# FPGA_MISC.net
KiCad netlist of a schematic drawn in Altium Designer
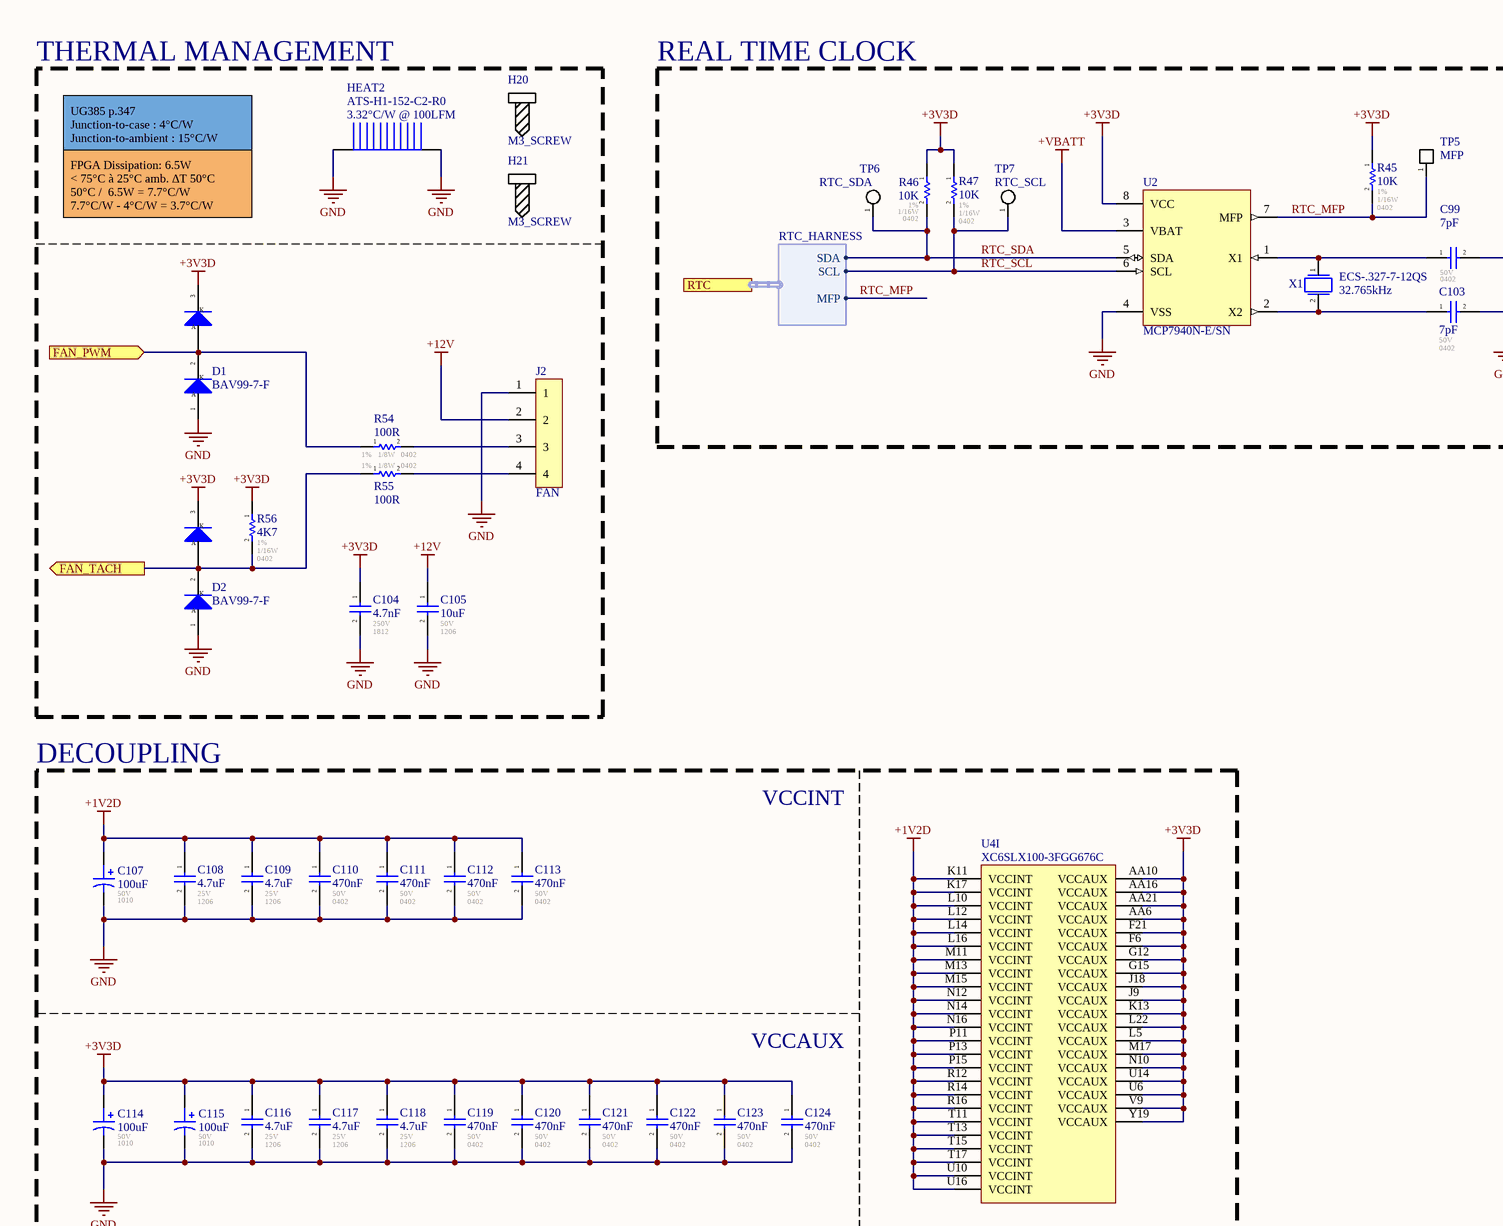
[diagram p0: FPGA_MISC.SchDoc, top left]
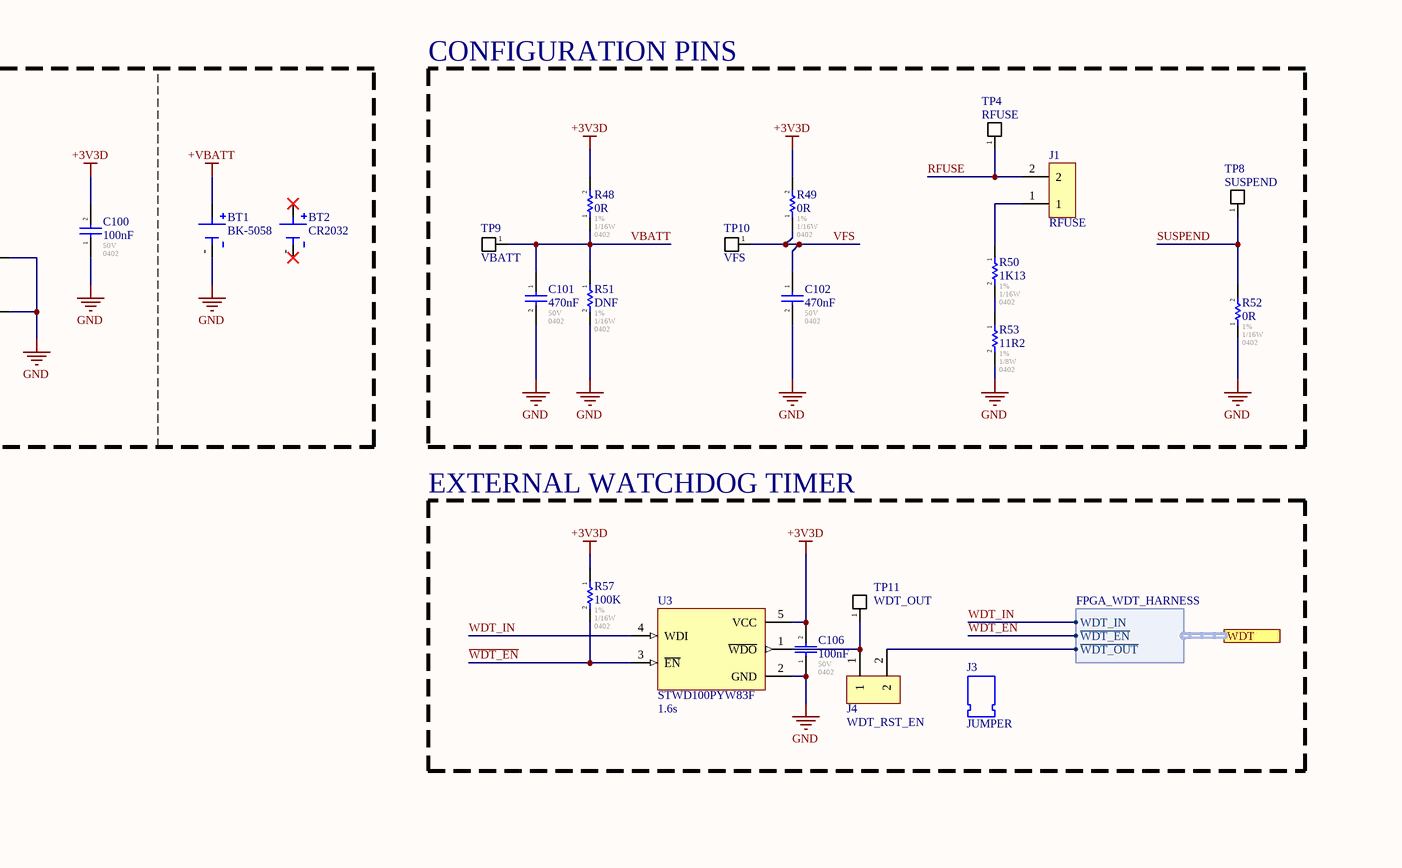
[diagram p1: FPGA_MISC.SchDoc, top right]
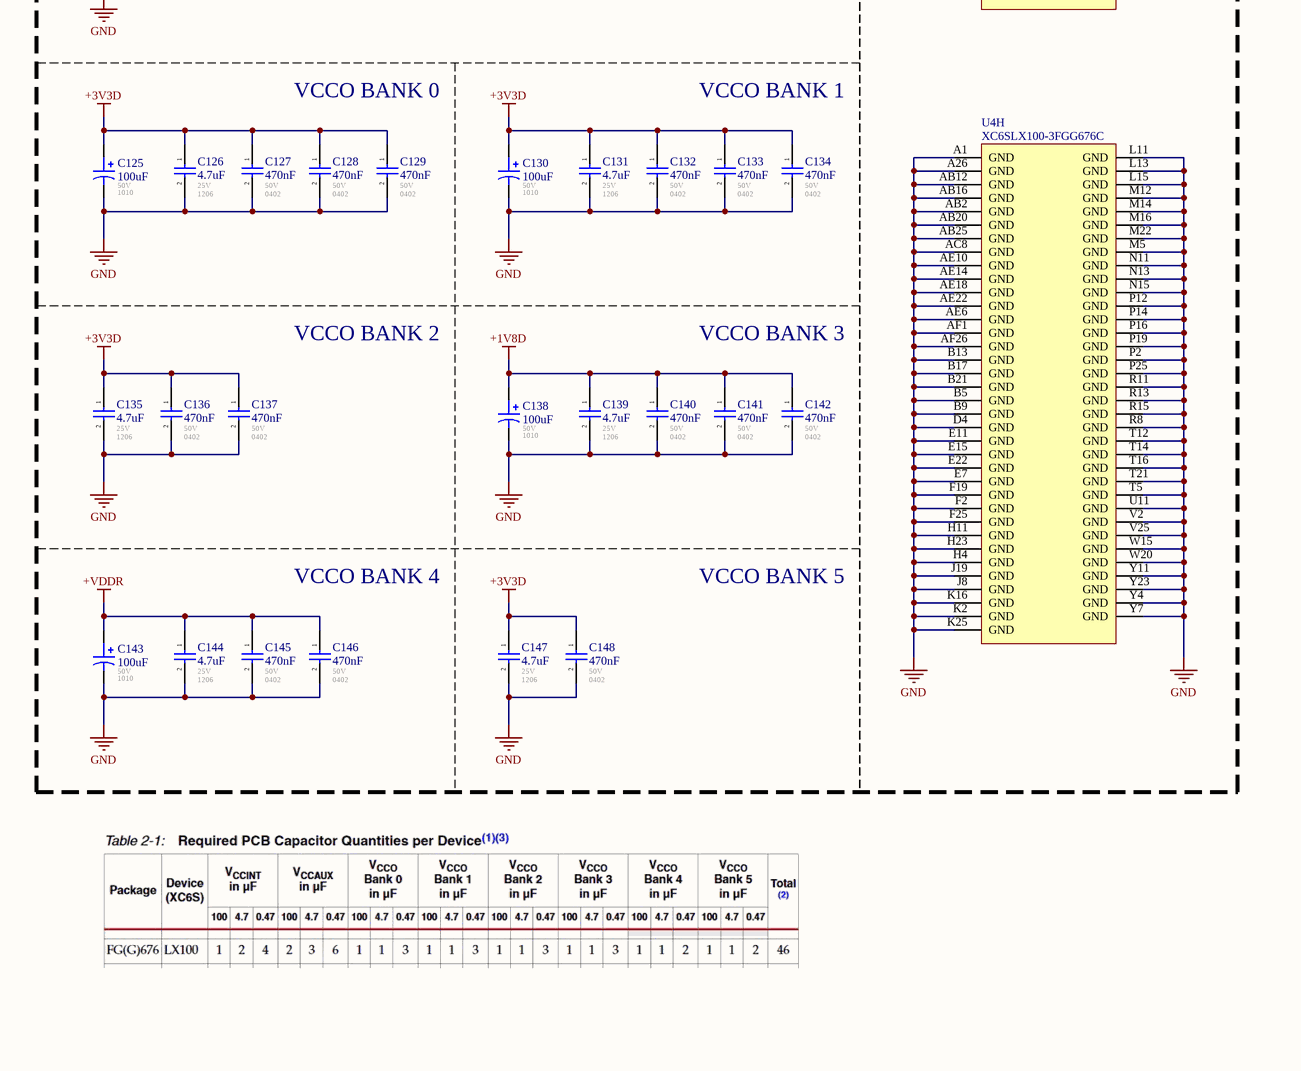
[diagram p2: FPGA_MISC.SchDoc, bottom left]
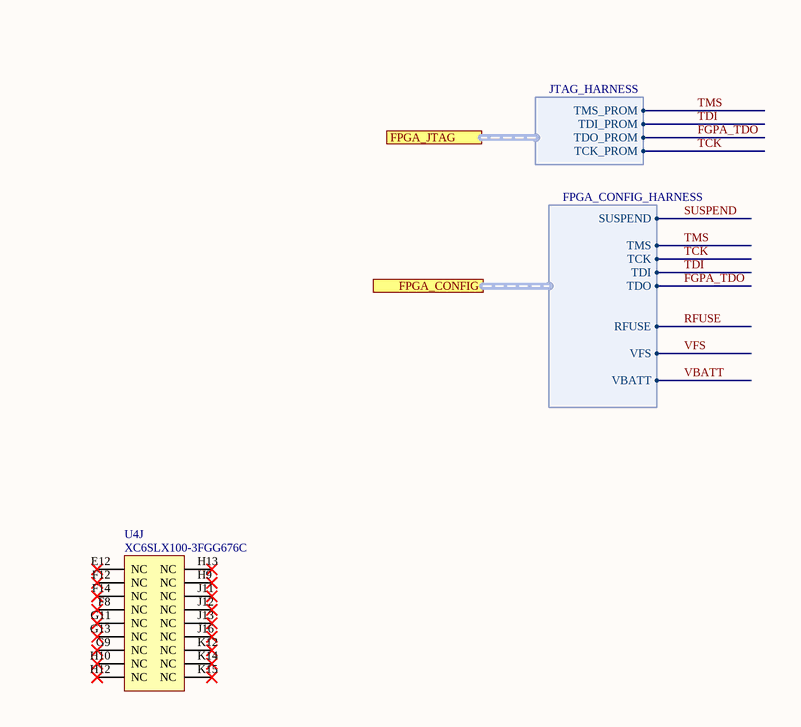
[diagram p3: FPGA_MISC.SchDoc, bottom right]

(export (version "E")
  (design (tool "Eeschema 10.0.6"))
  (components
    (comp (ref "BT1")
      (value "BK-5058")
      (footprint "BK-5058")
      (description "Battery Holder")
      (fields (field (name "MFR") "MPD"))
      (libsource (lib "Symbols") (part "BATTERY"))
    )
    (comp (ref "BT2") (value "CR2032") (libsource (lib "Symbols") (part "BATTERY")))
    (comp (ref "C99")
      (value "7pF")
      (footprint "0402")
      (description "0402 7pF C0G Ceramic Capacitor\r\nGCM1555C1H7R0BA16D")
      (fields (field (name "MFR") "Murata") (field (name "VOLTAGE - RATED") "50V"))
      (libsource (lib "Symbols") (part "CAP_CER"))
    )
    (comp (ref "C100")
      (value "100nF")
      (footprint "0402")
      (description "GCM155R71H104KE02J\r\n0402 100nF 10% X7R Ceramic Capacitor")
      (fields
        (field (name "MFR") "Murata")
        (field (name "PART#") "GCM155R71H104KE02J")
        (field (name "VOLTAGE - RATED") "50V")
      )
      (libsource (lib "Symbols") (part "CAP_CER"))
    )
    (comp (ref "C101")
      (value "470nF")
      (footprint "0402")
      (description "CGA3E3X7R1H474K080AB\r\n0603 470nF 10% X7R Ceramic Capacitor")
      (fields
        (field (name "MFR") "TDK")
        (field (name "PART#") "CGA3E3X7R1H474K080AB")
        (field (name "VOLTAGE - RATED") "50V")
      )
      (libsource (lib "Symbols") (part "CAP_CER"))
    )
    (comp (ref "C102")
      (value "470nF")
      (footprint "0402")
      (description "CGA3E3X7R1H474K080AB\r\n0603 470nF 10% X7R Ceramic Capacitor")
      (fields
        (field (name "MFR") "TDK")
        (field (name "PART#") "CGA3E3X7R1H474K080AB")
        (field (name "VOLTAGE - RATED") "50V")
      )
      (libsource (lib "Symbols") (part "CAP_CER"))
    )
    (comp (ref "C103")
      (value "7pF")
      (footprint "0402")
      (description "0402 7pF C0G Ceramic Capacitor\r\nGCM1555C1H7R0BA16D")
      (fields (field (name "MFR") "Murata") (field (name "VOLTAGE - RATED") "50V"))
      (libsource (lib "Symbols") (part "CAP_CER"))
    )
    (comp (ref "C104")
      (value "4.7nF")
      (footprint "1812")
      (description "GA343DR7GD472KW01L\r\n0402 4.7nF 10% X7R 1812 250VAC Ceramic Capacitor")
      (fields
        (field (name "MFR") "Murata")
        (field (name "VOLTAGE - RATED") "250V")
        (field (name "TOLERANCE") "10%")
      )
      (libsource (lib "Symbols") (part "CAP_CER"))
    )
    (comp (ref "C105")
      (value "10uF")
      (footprint "1206")
      (description "GRT31CR61H106KE01L\r\n1206 10uF 10% X5R Ceramic Capacitor")
      (fields
        (field (name "MFR") "Murata")
        (field (name "VOLTAGE - RATED") "50V")
        (field (name "TOLERANCE") "10%")
      )
      (libsource (lib "Symbols") (part "CAP_CER"))
    )
    (comp (ref "C106")
      (value "100nF")
      (footprint "0402")
      (description "GCM155R71H104KE02J\r\n0402 100nF 10% X7R Ceramic Capacitor")
      (fields
        (field (name "MFR") "Murata")
        (field (name "PART#") "GCM155R71H104KE02J")
        (field (name "VOLTAGE - RATED") "50V")
      )
      (libsource (lib "Symbols") (part "CAP_CER"))
    )
    (comp (ref "C107")
      (value "100uF")
      (footprint "CAP_ALU_1010_vishay")
      (description "CAP - ALU 100uF 20% 50V - 1010")
      (fields
        (field (name "MFG") "Vishay Dale")
        (field (name "MFG PART NUMBER") "MAL215099101E3")
        (field (name "VOLTAGE") "50V")
        (field (name "PACKAGE") "1010")
        (field (name "CREATEDBY") "Jonathan Bouchard")
      )
      (libsource (lib "S7CAS_LIB2023") (part "CAP_ALU_MAL215099101E3"))
    )
    (comp (ref "C108")
      (value "4.7uF")
      (footprint "1206")
      (description "CGA8L2X7R1E475M160KA\r\n1812 4.7uF 20% X7R Ceramic Capacitor")
      (fields
        (field (name "MFR") "TDK")
        (field (name "VOLTAGE - RATED") "25V")
        (field (name "TOLERANCE") "20%")
      )
      (libsource (lib "Symbols") (part "CAP_CER"))
    )
    (comp (ref "C109")
      (value "4.7uF")
      (footprint "1206")
      (description "CGA8L2X7R1E475M160KA\r\n1812 4.7uF 20% X7R Ceramic Capacitor")
      (fields
        (field (name "MFR") "TDK")
        (field (name "VOLTAGE - RATED") "25V")
        (field (name "TOLERANCE") "20%")
      )
      (libsource (lib "Symbols") (part "CAP_CER"))
    )
    (comp (ref "C110")
      (value "470nF")
      (footprint "0402")
      (description "CGA3E3X7R1H474K080AB\r\n0603 470nF 10% X7R Ceramic Capacitor")
      (fields
        (field (name "MFR") "TDK")
        (field (name "PART#") "CGA3E3X7R1H474K080AB")
        (field (name "VOLTAGE - RATED") "50V")
      )
      (libsource (lib "Symbols") (part "CAP_CER"))
    )
    (comp (ref "C111")
      (value "470nF")
      (footprint "0402")
      (description "CGA3E3X7R1H474K080AB\r\n0603 470nF 10% X7R Ceramic Capacitor")
      (fields
        (field (name "MFR") "TDK")
        (field (name "PART#") "CGA3E3X7R1H474K080AB")
        (field (name "VOLTAGE - RATED") "50V")
      )
      (libsource (lib "Symbols") (part "CAP_CER"))
    )
    (comp (ref "C112")
      (value "470nF")
      (footprint "0402")
      (description "CGA3E3X7R1H474K080AB\r\n0603 470nF 10% X7R Ceramic Capacitor")
      (fields
        (field (name "MFR") "TDK")
        (field (name "PART#") "CGA3E3X7R1H474K080AB")
        (field (name "VOLTAGE - RATED") "50V")
      )
      (libsource (lib "Symbols") (part "CAP_CER"))
    )
    (comp (ref "C113")
      (value "470nF")
      (footprint "0402")
      (description "CGA3E3X7R1H474K080AB\r\n0603 470nF 10% X7R Ceramic Capacitor")
      (fields
        (field (name "MFR") "TDK")
        (field (name "PART#") "CGA3E3X7R1H474K080AB")
        (field (name "VOLTAGE - RATED") "50V")
      )
      (libsource (lib "Symbols") (part "CAP_CER"))
    )
    (comp (ref "C114")
      (value "100uF")
      (footprint "CAP_ALU_1010_vishay")
      (description "CAP - ALU 100uF 20% 50V - 1010")
      (fields
        (field (name "MFG") "Vishay Dale")
        (field (name "MFG PART NUMBER") "MAL215099101E3")
        (field (name "VOLTAGE") "50V")
        (field (name "PACKAGE") "1010")
        (field (name "CREATEDBY") "Jonathan Bouchard")
      )
      (libsource (lib "S7CAS_LIB2023") (part "CAP_ALU_MAL215099101E3"))
    )
    (comp (ref "C115")
      (value "100uF")
      (footprint "CAP_ALU_1010_vishay")
      (description "CAP - ALU 100uF 20% 50V - 1010")
      (fields
        (field (name "MFG") "Vishay Dale")
        (field (name "MFG PART NUMBER") "MAL215099101E3")
        (field (name "VOLTAGE") "50V")
        (field (name "PACKAGE") "1010")
        (field (name "CREATEDBY") "Jonathan Bouchard")
      )
      (libsource (lib "S7CAS_LIB2023") (part "CAP_ALU_MAL215099101E3"))
    )
    (comp (ref "C116")
      (value "4.7uF")
      (footprint "1206")
      (description "CGA8L2X7R1E475M160KA\r\n1812 4.7uF 20% X7R Ceramic Capacitor")
      (fields
        (field (name "MFR") "TDK")
        (field (name "VOLTAGE - RATED") "25V")
        (field (name "TOLERANCE") "20%")
      )
      (libsource (lib "Symbols") (part "CAP_CER"))
    )
    (comp (ref "C117")
      (value "4.7uF")
      (footprint "1206")
      (description "CGA8L2X7R1E475M160KA\r\n1812 4.7uF 20% X7R Ceramic Capacitor")
      (fields
        (field (name "MFR") "TDK")
        (field (name "VOLTAGE - RATED") "25V")
        (field (name "TOLERANCE") "20%")
      )
      (libsource (lib "Symbols") (part "CAP_CER"))
    )
    (comp (ref "C118")
      (value "4.7uF")
      (footprint "1206")
      (description "CGA8L2X7R1E475M160KA\r\n1812 4.7uF 20% X7R Ceramic Capacitor")
      (fields
        (field (name "MFR") "TDK")
        (field (name "VOLTAGE - RATED") "25V")
        (field (name "TOLERANCE") "20%")
      )
      (libsource (lib "Symbols") (part "CAP_CER"))
    )
    (comp (ref "C119")
      (value "470nF")
      (footprint "0402")
      (description "CGA3E3X7R1H474K080AB\r\n0603 470nF 10% X7R Ceramic Capacitor")
      (fields
        (field (name "MFR") "TDK")
        (field (name "PART#") "CGA3E3X7R1H474K080AB")
        (field (name "VOLTAGE - RATED") "50V")
      )
      (libsource (lib "Symbols") (part "CAP_CER"))
    )
    (comp (ref "C120")
      (value "470nF")
      (footprint "0402")
      (description "CGA3E3X7R1H474K080AB\r\n0603 470nF 10% X7R Ceramic Capacitor")
      (fields
        (field (name "MFR") "TDK")
        (field (name "PART#") "CGA3E3X7R1H474K080AB")
        (field (name "VOLTAGE - RATED") "50V")
      )
      (libsource (lib "Symbols") (part "CAP_CER"))
    )
    (comp (ref "C121")
      (value "470nF")
      (footprint "0402")
      (description "CGA3E3X7R1H474K080AB\r\n0603 470nF 10% X7R Ceramic Capacitor")
      (fields
        (field (name "MFR") "TDK")
        (field (name "PART#") "CGA3E3X7R1H474K080AB")
        (field (name "VOLTAGE - RATED") "50V")
      )
      (libsource (lib "Symbols") (part "CAP_CER"))
    )
    (comp (ref "C122")
      (value "470nF")
      (footprint "0402")
      (description "CGA3E3X7R1H474K080AB\r\n0603 470nF 10% X7R Ceramic Capacitor")
      (fields
        (field (name "MFR") "TDK")
        (field (name "PART#") "CGA3E3X7R1H474K080AB")
        (field (name "VOLTAGE - RATED") "50V")
      )
      (libsource (lib "Symbols") (part "CAP_CER"))
    )
    (comp (ref "C123")
      (value "470nF")
      (footprint "0402")
      (description "CGA3E3X7R1H474K080AB\r\n0603 470nF 10% X7R Ceramic Capacitor")
      (fields
        (field (name "MFR") "TDK")
        (field (name "PART#") "CGA3E3X7R1H474K080AB")
        (field (name "VOLTAGE - RATED") "50V")
      )
      (libsource (lib "Symbols") (part "CAP_CER"))
    )
    (comp (ref "C124")
      (value "470nF")
      (footprint "0402")
      (description "CGA3E3X7R1H474K080AB\r\n0603 470nF 10% X7R Ceramic Capacitor")
      (fields
        (field (name "MFR") "TDK")
        (field (name "PART#") "CGA3E3X7R1H474K080AB")
        (field (name "VOLTAGE - RATED") "50V")
      )
      (libsource (lib "Symbols") (part "CAP_CER"))
    )
    (comp (ref "C125")
      (value "100uF")
      (footprint "CAP_ALU_1010_vishay")
      (description "CAP - ALU 100uF 20% 50V - 1010")
      (fields
        (field (name "MFG") "Vishay Dale")
        (field (name "MFG PART NUMBER") "MAL215099101E3")
        (field (name "VOLTAGE") "50V")
        (field (name "PACKAGE") "1010")
        (field (name "CREATEDBY") "Jonathan Bouchard")
      )
      (libsource (lib "S7CAS_LIB2023") (part "CAP_ALU_MAL215099101E3"))
    )
    (comp (ref "C126")
      (value "4.7uF")
      (footprint "1206")
      (description "CGA8L2X7R1E475M160KA\r\n1812 4.7uF 20% X7R Ceramic Capacitor")
      (fields
        (field (name "MFR") "TDK")
        (field (name "VOLTAGE - RATED") "25V")
        (field (name "TOLERANCE") "20%")
      )
      (libsource (lib "Symbols") (part "CAP_CER"))
    )
    (comp (ref "C127")
      (value "470nF")
      (footprint "0402")
      (description "CGA3E3X7R1H474K080AB\r\n0603 470nF 10% X7R Ceramic Capacitor")
      (fields
        (field (name "MFR") "TDK")
        (field (name "PART#") "CGA3E3X7R1H474K080AB")
        (field (name "VOLTAGE - RATED") "50V")
      )
      (libsource (lib "Symbols") (part "CAP_CER"))
    )
    (comp (ref "C128")
      (value "470nF")
      (footprint "0402")
      (description "CGA3E3X7R1H474K080AB\r\n0603 470nF 10% X7R Ceramic Capacitor")
      (fields
        (field (name "MFR") "TDK")
        (field (name "PART#") "CGA3E3X7R1H474K080AB")
        (field (name "VOLTAGE - RATED") "50V")
      )
      (libsource (lib "Symbols") (part "CAP_CER"))
    )
    (comp (ref "C129")
      (value "470nF")
      (footprint "0402")
      (description "CGA3E3X7R1H474K080AB\r\n0603 470nF 10% X7R Ceramic Capacitor")
      (fields
        (field (name "MFR") "TDK")
        (field (name "PART#") "CGA3E3X7R1H474K080AB")
        (field (name "VOLTAGE - RATED") "50V")
      )
      (libsource (lib "Symbols") (part "CAP_CER"))
    )
    (comp (ref "C130")
      (value "100uF")
      (footprint "CAP_ALU_1010_vishay")
      (description "CAP - ALU 100uF 20% 50V - 1010")
      (fields
        (field (name "MFG") "Vishay Dale")
        (field (name "MFG PART NUMBER") "MAL215099101E3")
        (field (name "VOLTAGE") "50V")
        (field (name "PACKAGE") "1010")
        (field (name "CREATEDBY") "Jonathan Bouchard")
      )
      (libsource (lib "S7CAS_LIB2023") (part "CAP_ALU_MAL215099101E3"))
    )
    (comp (ref "C131")
      (value "4.7uF")
      (footprint "1206")
      (description "CGA8L2X7R1E475M160KA\r\n1812 4.7uF 20% X7R Ceramic Capacitor")
      (fields
        (field (name "MFR") "TDK")
        (field (name "VOLTAGE - RATED") "25V")
        (field (name "TOLERANCE") "20%")
      )
      (libsource (lib "Symbols") (part "CAP_CER"))
    )
    (comp (ref "C132")
      (value "470nF")
      (footprint "0402")
      (description "CGA3E3X7R1H474K080AB\r\n0603 470nF 10% X7R Ceramic Capacitor")
      (fields
        (field (name "MFR") "TDK")
        (field (name "PART#") "CGA3E3X7R1H474K080AB")
        (field (name "VOLTAGE - RATED") "50V")
      )
      (libsource (lib "Symbols") (part "CAP_CER"))
    )
    (comp (ref "C133")
      (value "470nF")
      (footprint "0402")
      (description "CGA3E3X7R1H474K080AB\r\n0603 470nF 10% X7R Ceramic Capacitor")
      (fields
        (field (name "MFR") "TDK")
        (field (name "PART#") "CGA3E3X7R1H474K080AB")
        (field (name "VOLTAGE - RATED") "50V")
      )
      (libsource (lib "Symbols") (part "CAP_CER"))
    )
    (comp (ref "C134")
      (value "470nF")
      (footprint "0402")
      (description "CGA3E3X7R1H474K080AB\r\n0603 470nF 10% X7R Ceramic Capacitor")
      (fields
        (field (name "MFR") "TDK")
        (field (name "PART#") "CGA3E3X7R1H474K080AB")
        (field (name "VOLTAGE - RATED") "50V")
      )
      (libsource (lib "Symbols") (part "CAP_CER"))
    )
    (comp (ref "C135")
      (value "4.7uF")
      (footprint "1206")
      (description "CGA8L2X7R1E475M160KA\r\n1812 4.7uF 20% X7R Ceramic Capacitor")
      (fields
        (field (name "MFR") "TDK")
        (field (name "VOLTAGE - RATED") "25V")
        (field (name "TOLERANCE") "20%")
      )
      (libsource (lib "Symbols") (part "CAP_CER"))
    )
    (comp (ref "C136")
      (value "470nF")
      (footprint "0402")
      (description "CGA3E3X7R1H474K080AB\r\n0603 470nF 10% X7R Ceramic Capacitor")
      (fields
        (field (name "MFR") "TDK")
        (field (name "PART#") "CGA3E3X7R1H474K080AB")
        (field (name "VOLTAGE - RATED") "50V")
      )
      (libsource (lib "Symbols") (part "CAP_CER"))
    )
    (comp (ref "C137")
      (value "470nF")
      (footprint "0402")
      (description "CGA3E3X7R1H474K080AB\r\n0603 470nF 10% X7R Ceramic Capacitor")
      (fields
        (field (name "MFR") "TDK")
        (field (name "PART#") "CGA3E3X7R1H474K080AB")
        (field (name "VOLTAGE - RATED") "50V")
      )
      (libsource (lib "Symbols") (part "CAP_CER"))
    )
    (comp (ref "C138")
      (value "100uF")
      (footprint "CAP_ALU_1010_vishay")
      (description "CAP - ALU 100uF 20% 50V - 1010")
      (fields
        (field (name "MFG") "Vishay Dale")
        (field (name "MFG PART NUMBER") "MAL215099101E3")
        (field (name "VOLTAGE") "50V")
        (field (name "PACKAGE") "1010")
        (field (name "CREATEDBY") "Jonathan Bouchard")
      )
      (libsource (lib "S7CAS_LIB2023") (part "CAP_ALU_MAL215099101E3"))
    )
    (comp (ref "C139")
      (value "4.7uF")
      (footprint "1206")
      (description "CGA8L2X7R1E475M160KA\r\n1812 4.7uF 20% X7R Ceramic Capacitor")
      (fields
        (field (name "MFR") "TDK")
        (field (name "VOLTAGE - RATED") "25V")
        (field (name "TOLERANCE") "20%")
      )
      (libsource (lib "Symbols") (part "CAP_CER"))
    )
    (comp (ref "C140")
      (value "470nF")
      (footprint "0402")
      (description "CGA3E3X7R1H474K080AB\r\n0603 470nF 10% X7R Ceramic Capacitor")
      (fields
        (field (name "MFR") "TDK")
        (field (name "PART#") "CGA3E3X7R1H474K080AB")
        (field (name "VOLTAGE - RATED") "50V")
      )
      (libsource (lib "Symbols") (part "CAP_CER"))
    )
    (comp (ref "C141")
      (value "470nF")
      (footprint "0402")
      (description "CGA3E3X7R1H474K080AB\r\n0603 470nF 10% X7R Ceramic Capacitor")
      (fields
        (field (name "MFR") "TDK")
        (field (name "PART#") "CGA3E3X7R1H474K080AB")
        (field (name "VOLTAGE - RATED") "50V")
      )
      (libsource (lib "Symbols") (part "CAP_CER"))
    )
    (comp (ref "C142")
      (value "470nF")
      (footprint "0402")
      (description "CGA3E3X7R1H474K080AB\r\n0603 470nF 10% X7R Ceramic Capacitor")
      (fields
        (field (name "MFR") "TDK")
        (field (name "PART#") "CGA3E3X7R1H474K080AB")
        (field (name "VOLTAGE - RATED") "50V")
      )
      (libsource (lib "Symbols") (part "CAP_CER"))
    )
    (comp (ref "C143")
      (value "100uF")
      (footprint "CAP_ALU_1010_vishay")
      (description "CAP - ALU 100uF 20% 50V - 1010")
      (fields
        (field (name "MFG") "Vishay Dale")
        (field (name "MFG PART NUMBER") "MAL215099101E3")
        (field (name "VOLTAGE") "50V")
        (field (name "PACKAGE") "1010")
        (field (name "CREATEDBY") "Jonathan Bouchard")
      )
      (libsource (lib "S7CAS_LIB2023") (part "CAP_ALU_MAL215099101E3"))
    )
    (comp (ref "C144")
      (value "4.7uF")
      (footprint "1206")
      (description "CGA8L2X7R1E475M160KA\r\n1812 4.7uF 20% X7R Ceramic Capacitor")
      (fields
        (field (name "MFR") "TDK")
        (field (name "VOLTAGE - RATED") "25V")
        (field (name "TOLERANCE") "20%")
      )
      (libsource (lib "Symbols") (part "CAP_CER"))
    )
    (comp (ref "C145")
      (value "470nF")
      (footprint "0402")
      (description "CGA3E3X7R1H474K080AB\r\n0603 470nF 10% X7R Ceramic Capacitor")
      (fields
        (field (name "MFR") "TDK")
        (field (name "PART#") "CGA3E3X7R1H474K080AB")
        (field (name "VOLTAGE - RATED") "50V")
      )
      (libsource (lib "Symbols") (part "CAP_CER"))
    )
    (comp (ref "C146")
      (value "470nF")
      (footprint "0402")
      (description "CGA3E3X7R1H474K080AB\r\n0603 470nF 10% X7R Ceramic Capacitor")
      (fields
        (field (name "MFR") "TDK")
        (field (name "PART#") "CGA3E3X7R1H474K080AB")
        (field (name "VOLTAGE - RATED") "50V")
      )
      (libsource (lib "Symbols") (part "CAP_CER"))
    )
    (comp (ref "C147")
      (value "4.7uF")
      (footprint "1206")
      (description "CGA8L2X7R1E475M160KA\r\n1812 4.7uF 20% X7R Ceramic Capacitor")
      (fields
        (field (name "MFR") "TDK")
        (field (name "VOLTAGE - RATED") "25V")
        (field (name "TOLERANCE") "20%")
      )
      (libsource (lib "Symbols") (part "CAP_CER"))
    )
    (comp (ref "C148")
      (value "470nF")
      (footprint "0402")
      (description "CGA3E3X7R1H474K080AB\r\n0603 470nF 10% X7R Ceramic Capacitor")
      (fields
        (field (name "MFR") "TDK")
        (field (name "PART#") "CGA3E3X7R1H474K080AB")
        (field (name "VOLTAGE - RATED") "50V")
      )
      (libsource (lib "Symbols") (part "CAP_CER"))
    )
    (comp (ref "D1")
      (value "BAV99-7-F")
      (footprint "SOT23-3")
      (description "Diode Array 1 Pair Series Connection 75 V 300mA (DC) Surface Mount TO-236-3, SC-59, SOT-23-3")
      (fields (field (name "MFR") "Diodes Incorporated"))
      (libsource (lib "Symbols") (part "DIODE_TVS_DUAL"))
    )
    (comp (ref "D2")
      (value "BAV99-7-F")
      (footprint "SOT23-3")
      (description "Diode Array 1 Pair Series Connection 75 V 300mA (DC) Surface Mount TO-236-3, SC-59, SOT-23-3")
      (fields (field (name "MFR") "Diodes Incorporated"))
      (libsource (lib "Symbols") (part "DIODE_TVS_DUAL"))
    )
    (comp (ref "H20") (value "M3_SCREW") (libsource (lib "Misc") (part "M3_screw")))
    (comp (ref "H21") (value "M3_SCREW") (libsource (lib "Misc") (part "M3_screw")))
    (comp (ref "HEAT2")
      (value "ATS-H1-152-C2-R0")
      (footprint "ATS-H1-152-C2-R0")
      (description "Heatsink Aluminium")
      (fields
        (field (name "MFR") "Advanced Thermal Solutions Inc.")
        (field (name "THERMAL RESISTANCE") "3.32°C/W @ 100LFM")
      )
      (libsource (lib "Misc") (part "HEATSINK_ATS-H1-152-C2-R0"))
    )
    (comp (ref "J1")
      (value "RFUSE")
      (footprint "HEADER-2_100MIL")
      (libsource (lib "Connectors") (part "HEADER_2"))
    )
    (comp (ref "J2")
      (value "FAN")
      (footprint "FAN_HEADER-4")
      (libsource (lib "Connectors") (part "HEADER_4"))
    )
    (comp (ref "J3") (value "JUMPER") (libsource (lib "Misc") (part "JUMPER")))
    (comp (ref "J4")
      (value "WDT_RST_EN")
      (footprint "HEADER-2_100MIL")
      (libsource (lib "") (part "HEADER_2_1"))
    )
    (comp (ref "R45")
      (value "10K")
      (footprint "RES_0402")
      (fields
        (field (name "TOLERANCE") "1%")
        (field (name "POWER") "1/16W")
        (field (name "PACKAGE / CASE") "0402")
      )
      (libsource (lib "Symbols") (part "RESISTOR"))
    )
    (comp (ref "R46")
      (value "10K")
      (footprint "RES_0402")
      (fields
        (field (name "TOLERANCE") "1%")
        (field (name "POWER") "1/16W")
        (field (name "PACKAGE / CASE") "0402")
      )
      (libsource (lib "Symbols") (part "RESISTOR"))
    )
    (comp (ref "R47")
      (value "10K")
      (footprint "RES_0402")
      (fields
        (field (name "TOLERANCE") "1%")
        (field (name "POWER") "1/16W")
        (field (name "PACKAGE / CASE") "0402")
      )
      (libsource (lib "Symbols") (part "RESISTOR"))
    )
    (comp (ref "R48")
      (value "0R")
      (footprint "RES_0402")
      (fields
        (field (name "TOLERANCE") "1%")
        (field (name "POWER") "1/16W")
        (field (name "PACKAGE / CASE") "0402")
      )
      (libsource (lib "Symbols") (part "RESISTOR"))
    )
    (comp (ref "R49")
      (value "0R")
      (footprint "RES_0402")
      (fields
        (field (name "TOLERANCE") "1%")
        (field (name "POWER") "1/16W")
        (field (name "PACKAGE / CASE") "0402")
      )
      (libsource (lib "Symbols") (part "RESISTOR"))
    )
    (comp (ref "R50")
      (value "1K13")
      (footprint "RES_0402")
      (fields
        (field (name "TOLERANCE") "1%")
        (field (name "POWER") "1/16W")
        (field (name "PACKAGE / CASE") "0402")
      )
      (libsource (lib "Symbols") (part "RESISTOR"))
    )
    (comp (ref "R51")
      (value "DNF")
      (footprint "RES_0402")
      (fields
        (field (name "TOLERANCE") "1%")
        (field (name "POWER") "1/16W")
        (field (name "PACKAGE / CASE") "0402")
      )
      (libsource (lib "Symbols") (part "RESISTOR"))
    )
    (comp (ref "R52")
      (value "0R")
      (footprint "RES_0402")
      (fields
        (field (name "TOLERANCE") "1%")
        (field (name "POWER") "1/16W")
        (field (name "PACKAGE / CASE") "0402")
      )
      (libsource (lib "Symbols") (part "RESISTOR"))
    )
    (comp (ref "R53")
      (value "11R2")
      (footprint "RES_0402")
      (fields
        (field (name "TOLERANCE") "1%")
        (field (name "POWER") "1/8W")
        (field (name "PACKAGE / CASE") "0402")
      )
      (libsource (lib "Symbols") (part "RESISTOR"))
    )
    (comp (ref "R54")
      (value "100R")
      (footprint "RES_0402")
      (fields
        (field (name "TOLERANCE") "1%")
        (field (name "POWER") "1/8W")
        (field (name "PACKAGE / CASE") "0402")
      )
      (libsource (lib "Symbols") (part "RESISTOR"))
    )
    (comp (ref "R55")
      (value "100R")
      (footprint "RES_0402")
      (fields
        (field (name "TOLERANCE") "1%")
        (field (name "POWER") "1/8W")
        (field (name "PACKAGE / CASE") "0402")
      )
      (libsource (lib "Symbols") (part "RESISTOR"))
    )
    (comp (ref "R56")
      (value "4K7")
      (footprint "RES_0402")
      (fields
        (field (name "TOLERANCE") "1%")
        (field (name "POWER") "1/16W")
        (field (name "PACKAGE / CASE") "0402")
      )
      (libsource (lib "Symbols") (part "RESISTOR"))
    )
    (comp (ref "R57")
      (value "100K")
      (footprint "RES_0402")
      (fields
        (field (name "TOLERANCE") "1%")
        (field (name "POWER") "1/16W")
        (field (name "PACKAGE / CASE") "0402")
      )
      (libsource (lib "Symbols") (part "RESISTOR"))
    )
    (comp (ref "TP4")
      (value "RFUSE")
      (footprint "TP_PAD")
      (description "Test Point")
      (libsource (lib "Symbols") (part "TESTPOINT_PAD"))
    )
    (comp (ref "TP5")
      (value "MFP")
      (footprint "TP_PAD")
      (description "Test Point")
      (libsource (lib "Symbols") (part "TESTPOINT_PAD"))
    )
    (comp (ref "TP6")
      (value "RTC_SDA")
      (footprint "TP_PAD_SMALL")
      (description "Test Point")
      (libsource (lib "Symbols") (part "TESTPOINT_PAD_SMALL"))
    )
    (comp (ref "TP7")
      (value "RTC_SCL")
      (footprint "TP_PAD_SMALL")
      (description "Test Point")
      (libsource (lib "Symbols") (part "TESTPOINT_PAD_SMALL"))
    )
    (comp (ref "TP8")
      (value "SUSPEND")
      (footprint "TP_PAD")
      (description "Test Point")
      (libsource (lib "Symbols") (part "TESTPOINT_PAD"))
    )
    (comp (ref "TP9")
      (value "VBATT")
      (footprint "TP_PAD")
      (description "Test Point")
      (libsource (lib "Symbols") (part "TESTPOINT_PAD"))
    )
    (comp (ref "TP10")
      (value "VFS")
      (footprint "TP_PAD")
      (description "Test Point")
      (libsource (lib "Symbols") (part "TESTPOINT_PAD"))
    )
    (comp (ref "TP11")
      (value "WDT_OUT")
      (footprint "TP_PAD")
      (description "Test Point")
      (libsource (lib "Symbols") (part "TESTPOINT_PAD"))
    )
    (comp (ref "U2")
      (value "MCP7940N-E/SN")
      (footprint "SOIC-8_3.8mm")
      (description "Real Time Clock (RTC) IC Clock/Calendar 64B I2C, 2-Wire Serial 8-SOIC (0.154\", 3.90mm Width)")
      (fields (field (name "MFR") "Microchip"))
      (libsource (lib "Misc") (part "MCP7940N-E/SN"))
    )
    (comp (ref "U3")
      (value "STWD100PYW83F")
      (footprint "SOT23-5")
      (description "WATCHDOG CIRCUIT\r\nIC SUPERVISOR 1 CHANNEL SOT23-5")
      (fields (field (name "MFR") "ST") (field (name "RESET TIMEOUT") "1.6s"))
      (libsource (lib "Misc") (part "STWD100PYW83F"))
    )
    (comp (ref "U4")
      (value "XC6SLX100-3FGG676C")
      (footprint "FPGA_XILINX_FGG676")
      (description "FPGA - XILINX SPARTAN 6 480 I/O - BGA-676")
      (fields
        (field (name "VOLTAGE") "1.14 V ~ 1.26 V")
        (field (name "MFG") "Xilinx")
        (field (name "CREATEDBY") "Jonathan Bouchard")
      )
      (libsource (lib "S7CAS_LIB2023") (part "FPGA_XC6SLX100-3FGG676C"))
    )
    (comp (ref "X1")
      (value "ECS-.327-7-12QS")
      (footprint "ECX-12Q-2MMx1.2MM")
      (description "25 MHz ±30ppm Crystal 16pF 40 Ohms HC-49/US")
      (fields (field (name "FREQUENCY") "32.765kHz"))
      (libsource (lib "Symbols") (part "OSCILLATOR"))
    )
  )
  (nets
    (net (code "5") (name "+1V2D") (class "Default")
      (node (ref "C107") (pin "1") (pinfunction "1_1") (pintype "passive"))
      (node (ref "C108") (pin "1") (pinfunction "1_1") (pintype "passive"))
      (node (ref "C109") (pin "1") (pinfunction "1_1") (pintype "passive"))
      (node (ref "C110") (pin "1") (pinfunction "1_1") (pintype "passive"))
      (node (ref "C111") (pin "1") (pinfunction "1_1") (pintype "passive"))
      (node (ref "C112") (pin "1") (pinfunction "1_1") (pintype "passive"))
      (node (ref "C113") (pin "1") (pinfunction "1_1") (pintype "passive"))
      (node (ref "U4") (pin "K11") (pinfunction "VCCINT_K11") (pintype "power_in"))
      (node (ref "U4") (pin "K17") (pinfunction "VCCINT_K17") (pintype "power_in"))
      (node (ref "U4") (pin "L10") (pinfunction "VCCINT_L10") (pintype "power_in"))
      (node (ref "U4") (pin "L12") (pinfunction "VCCINT_L12") (pintype "power_in"))
      (node (ref "U4") (pin "L14") (pinfunction "VCCINT_L14") (pintype "power_in"))
      (node (ref "U4") (pin "L16") (pinfunction "VCCINT_L16") (pintype "power_in"))
      (node (ref "U4") (pin "M11") (pinfunction "VCCINT_M11") (pintype "power_in"))
      (node (ref "U4") (pin "M13") (pinfunction "VCCINT_M13") (pintype "power_in"))
      (node (ref "U4") (pin "M15") (pinfunction "VCCINT_M15") (pintype "power_in"))
      (node (ref "U4") (pin "N12") (pinfunction "VCCINT_N12") (pintype "power_in"))
      (node (ref "U4") (pin "N14") (pinfunction "VCCINT_N14") (pintype "power_in"))
      (node (ref "U4") (pin "N16") (pinfunction "VCCINT_N16") (pintype "power_in"))
      (node (ref "U4") (pin "P11") (pinfunction "VCCINT_P11") (pintype "power_in"))
      (node (ref "U4") (pin "P13") (pinfunction "VCCINT_P13") (pintype "power_in"))
      (node (ref "U4") (pin "P15") (pinfunction "VCCINT_P15") (pintype "power_in"))
      (node (ref "U4") (pin "R12") (pinfunction "VCCINT_R12") (pintype "power_in"))
      (node (ref "U4") (pin "R14") (pinfunction "VCCINT_R14") (pintype "power_in"))
      (node (ref "U4") (pin "R16") (pinfunction "VCCINT_R16") (pintype "power_in"))
      (node (ref "U4") (pin "T11") (pinfunction "VCCINT_T11") (pintype "power_in"))
      (node (ref "U4") (pin "T13") (pinfunction "VCCINT_T13") (pintype "power_in"))
      (node (ref "U4") (pin "T15") (pinfunction "VCCINT_T15") (pintype "power_in"))
      (node (ref "U4") (pin "T17") (pinfunction "VCCINT_T17") (pintype "power_in"))
      (node (ref "U4") (pin "U10") (pinfunction "VCCINT_U10") (pintype "power_in"))
      (node (ref "U4") (pin "U16") (pinfunction "VCCINT_U16") (pintype "power_in"))
    )
    (net (code "6") (name "+1V8D") (class "Default")
      (node (ref "C138") (pin "1") (pinfunction "1_1") (pintype "passive"))
      (node (ref "C139") (pin "1") (pinfunction "1_1") (pintype "passive"))
      (node (ref "C140") (pin "1") (pinfunction "1_1") (pintype "passive"))
      (node (ref "C141") (pin "1") (pinfunction "1_1") (pintype "passive"))
      (node (ref "C142") (pin "1") (pinfunction "1_1") (pintype "passive"))
    )
    (net (code "7") (name "+3V3D") (class "Default")
      (node (ref "C100") (pin "2") (pinfunction "2_2") (pintype "passive"))
      (node (ref "C104") (pin "1") (pinfunction "1_1") (pintype "passive"))
      (node (ref "C106") (pin "2") (pinfunction "2_2") (pintype "passive"))
      (node (ref "C114") (pin "1") (pinfunction "1_1") (pintype "passive"))
      (node (ref "C115") (pin "1") (pinfunction "1_1") (pintype "passive"))
      (node (ref "C116") (pin "1") (pinfunction "1_1") (pintype "passive"))
      (node (ref "C117") (pin "1") (pinfunction "1_1") (pintype "passive"))
      (node (ref "C118") (pin "1") (pinfunction "1_1") (pintype "passive"))
      (node (ref "C119") (pin "1") (pinfunction "1_1") (pintype "passive"))
      (node (ref "C120") (pin "1") (pinfunction "1_1") (pintype "passive"))
      (node (ref "C121") (pin "1") (pinfunction "1_1") (pintype "passive"))
      (node (ref "C122") (pin "1") (pinfunction "1_1") (pintype "passive"))
      (node (ref "C123") (pin "1") (pinfunction "1_1") (pintype "passive"))
      (node (ref "C124") (pin "1") (pinfunction "1_1") (pintype "passive"))
      (node (ref "C125") (pin "1") (pinfunction "1_1") (pintype "passive"))
      (node (ref "C126") (pin "1") (pinfunction "1_1") (pintype "passive"))
      (node (ref "C127") (pin "1") (pinfunction "1_1") (pintype "passive"))
      (node (ref "C128") (pin "1") (pinfunction "1_1") (pintype "passive"))
      (node (ref "C129") (pin "1") (pinfunction "1_1") (pintype "passive"))
      (node (ref "C130") (pin "1") (pinfunction "1_1") (pintype "passive"))
      (node (ref "C131") (pin "1") (pinfunction "1_1") (pintype "passive"))
      (node (ref "C132") (pin "1") (pinfunction "1_1") (pintype "passive"))
      (node (ref "C133") (pin "1") (pinfunction "1_1") (pintype "passive"))
      (node (ref "C134") (pin "1") (pinfunction "1_1") (pintype "passive"))
      (node (ref "C135") (pin "1") (pinfunction "1_1") (pintype "passive"))
      (node (ref "C136") (pin "1") (pinfunction "1_1") (pintype "passive"))
      (node (ref "C137") (pin "1") (pinfunction "1_1") (pintype "passive"))
      (node (ref "C147") (pin "1") (pinfunction "1_1") (pintype "passive"))
      (node (ref "C148") (pin "1") (pinfunction "1_1") (pintype "passive"))
      (node (ref "D1") (pin "3") (pinfunction "K_3") (pintype "passive"))
      (node (ref "D2") (pin "3") (pinfunction "K_3") (pintype "passive"))
      (node (ref "R45") (pin "1") (pinfunction "1_1") (pintype "passive"))
      (node (ref "R46") (pin "1") (pinfunction "1_1") (pintype "passive"))
      (node (ref "R47") (pin "1") (pinfunction "1_1") (pintype "passive"))
      (node (ref "R48") (pin "2") (pinfunction "2_2") (pintype "passive"))
      (node (ref "R49") (pin "2") (pinfunction "2_2") (pintype "passive"))
      (node (ref "R56") (pin "1") (pinfunction "1_1") (pintype "passive"))
      (node (ref "R57") (pin "1") (pinfunction "1_1") (pintype "passive"))
      (node (ref "U2") (pin "8") (pinfunction "VCC_8") (pintype "power_in"))
      (node (ref "U3") (pin "5") (pinfunction "VCC_5") (pintype "power_in"))
      (node (ref "U4") (pin "AA10") (pinfunction "VCCAUX_AA10") (pintype "power_in"))
      (node (ref "U4") (pin "AA16") (pinfunction "VCCAUX_AA16") (pintype "power_in"))
      (node (ref "U4") (pin "AA21") (pinfunction "VCCAUX_AA21") (pintype "power_in"))
      (node (ref "U4") (pin "AA6") (pinfunction "VCCAUX_AA6") (pintype "power_in"))
      (node (ref "U4") (pin "F21") (pinfunction "VCCAUX_F21") (pintype "power_in"))
      (node (ref "U4") (pin "F6") (pinfunction "VCCAUX_F6") (pintype "power_in"))
      (node (ref "U4") (pin "G12") (pinfunction "VCCAUX_G12") (pintype "power_in"))
      (node (ref "U4") (pin "G15") (pinfunction "VCCAUX_G15") (pintype "power_in"))
      (node (ref "U4") (pin "J18") (pinfunction "VCCAUX_J18") (pintype "power_in"))
      (node (ref "U4") (pin "J9") (pinfunction "VCCAUX_J9") (pintype "power_in"))
      (node (ref "U4") (pin "K13") (pinfunction "VCCAUX_K13") (pintype "power_in"))
      (node (ref "U4") (pin "L22") (pinfunction "VCCAUX_L22") (pintype "power_in"))
      (node (ref "U4") (pin "L5") (pinfunction "VCCAUX_L5") (pintype "power_in"))
      (node (ref "U4") (pin "M17") (pinfunction "VCCAUX_M17") (pintype "power_in"))
      (node (ref "U4") (pin "N10") (pinfunction "VCCAUX_N10") (pintype "power_in"))
      (node (ref "U4") (pin "U14") (pinfunction "VCCAUX_U14") (pintype "power_in"))
      (node (ref "U4") (pin "U6") (pinfunction "VCCAUX_U6") (pintype "power_in"))
      (node (ref "U4") (pin "V9") (pinfunction "VCCAUX_V9") (pintype "power_in"))
      (node (ref "U4") (pin "Y19") (pinfunction "VCCAUX_Y19") (pintype "power_in"))
    )
    (net (code "8") (name "+12V") (class "Default")
      (node (ref "C105") (pin "1") (pinfunction "1_1") (pintype "passive"))
      (node (ref "J2") (pin "2") (pinfunction "2_2") (pintype "passive"))
    )
    (net (code "9") (name "+VBATT") (class "Default")
      (node (ref "BT1") (pin "+") (pinfunction "+_+") (pintype "power_in"))
      (node (ref "U2") (pin "3") (pinfunction "VBAT_3") (pintype "power_in"))
    )
    (net (code "10") (name "+VDDR") (class "Default")
      (node (ref "C143") (pin "1") (pinfunction "1_1") (pintype "passive"))
      (node (ref "C144") (pin "1") (pinfunction "1_1") (pintype "passive"))
      (node (ref "C145") (pin "1") (pinfunction "1_1") (pintype "passive"))
      (node (ref "C146") (pin "1") (pinfunction "1_1") (pintype "passive"))
    )
    (net (code "11") (name "/FAN_PWM") (class "Default")
      (node (ref "D1") (pin "2") (pinfunction "K_2") (pintype "passive"))
      (node (ref "R54") (pin "1") (pinfunction "1_1") (pintype "passive"))
    )
    (net (code "12") (name "/FAN_TACH") (class "Default")
      (node (ref "D2") (pin "2") (pinfunction "K_2") (pintype "passive"))
      (node (ref "R55") (pin "1") (pinfunction "1_1") (pintype "passive"))
      (node (ref "R56") (pin "2") (pinfunction "2_2") (pintype "passive"))
    )
    (net (code "14") (name "/RFUSE") (class "Default")
      (node (ref "J1") (pin "2") (pinfunction "2_2") (pintype "passive"))
      (node (ref "TP4") (pin "1") (pinfunction "A_1") (pintype "passive"))
    )
    (net (code "15") (name "/RTC_MFP") (class "Default")
      (node (ref "R45") (pin "2") (pinfunction "2_2") (pintype "passive"))
      (node (ref "TP5") (pin "1") (pinfunction "A_1") (pintype "passive"))
      (node (ref "U2") (pin "7") (pinfunction "MFP_7") (pintype "output"))
    )
    (net (code "16") (name "/RTC_SCL") (class "Default")
      (node (ref "R47") (pin "2") (pinfunction "2_2") (pintype "passive"))
      (node (ref "TP7") (pin "1") (pinfunction "A_1") (pintype "passive"))
      (node (ref "U2") (pin "6") (pinfunction "SCL_6") (pintype "input"))
    )
    (net (code "17") (name "/RTC_SDA") (class "Default")
      (node (ref "R46") (pin "2") (pinfunction "2_2") (pintype "passive"))
      (node (ref "TP6") (pin "1") (pinfunction "A_1") (pintype "passive"))
      (node (ref "U2") (pin "5") (pinfunction "SDA_5") (pintype "bidirectional"))
    )
    (net (code "18") (name "/SUSPEND") (class "Default")
      (node (ref "R52") (pin "2") (pinfunction "2_2") (pintype "passive"))
      (node (ref "TP8") (pin "1") (pinfunction "A_1") (pintype "passive"))
    )
    (net (code "22") (name "/VBATT") (class "Default")
      (node (ref "C101") (pin "1") (pinfunction "1_1") (pintype "passive"))
      (node (ref "R48") (pin "1") (pinfunction "1_1") (pintype "passive"))
      (node (ref "R51") (pin "1") (pinfunction "1_1") (pintype "passive"))
      (node (ref "TP9") (pin "1") (pinfunction "A_1") (pintype "passive"))
    )
    (net (code "23") (name "/VFS") (class "Default")
      (node (ref "C102") (pin "1") (pinfunction "1_1") (pintype "passive"))
      (node (ref "R49") (pin "1") (pinfunction "1_1") (pintype "passive"))
      (node (ref "TP10") (pin "1") (pinfunction "A_1") (pintype "passive"))
    )
    (net (code "24") (name "/WDT_EN") (class "Default")
      (node (ref "R57") (pin "2") (pinfunction "2_2") (pintype "passive"))
      (node (ref "U3") (pin "3") (pinfunction "EN_3") (pintype "input"))
    )
    (net (code "25") (name "/WDT_IN") (class "Default")
      (node (ref "U3") (pin "4") (pinfunction "WDI_4") (pintype "input"))
    )
    (net (code "30") (name "/~{WDT_OUT}") (class "Default")
      (node (ref "J4") (pin "2") (pinfunction "2_2") (pintype "passive"))
    )
    (net (code "31") (name "GND") (class "Default")
      (node (ref "BT1") (pin "-") (pinfunction "-_-") (pintype "power_in"))
      (node (ref "C100") (pin "1") (pinfunction "1_1") (pintype "passive"))
      (node (ref "C101") (pin "2") (pinfunction "2_2") (pintype "passive"))
      (node (ref "C102") (pin "2") (pinfunction "2_2") (pintype "passive"))
      (node (ref "C103") (pin "2") (pinfunction "2_2") (pintype "passive"))
      (node (ref "C104") (pin "2") (pinfunction "2_2") (pintype "passive"))
      (node (ref "C105") (pin "2") (pinfunction "2_2") (pintype "passive"))
      (node (ref "C106") (pin "1") (pinfunction "1_1") (pintype "passive"))
      (node (ref "C107") (pin "2") (pinfunction "2_2") (pintype "passive"))
      (node (ref "C108") (pin "2") (pinfunction "2_2") (pintype "passive"))
      (node (ref "C109") (pin "2") (pinfunction "2_2") (pintype "passive"))
      (node (ref "C110") (pin "2") (pinfunction "2_2") (pintype "passive"))
      (node (ref "C111") (pin "2") (pinfunction "2_2") (pintype "passive"))
      (node (ref "C112") (pin "2") (pinfunction "2_2") (pintype "passive"))
      (node (ref "C113") (pin "2") (pinfunction "2_2") (pintype "passive"))
      (node (ref "C114") (pin "2") (pinfunction "2_2") (pintype "passive"))
      (node (ref "C115") (pin "2") (pinfunction "2_2") (pintype "passive"))
      (node (ref "C116") (pin "2") (pinfunction "2_2") (pintype "passive"))
      (node (ref "C117") (pin "2") (pinfunction "2_2") (pintype "passive"))
      (node (ref "C118") (pin "2") (pinfunction "2_2") (pintype "passive"))
      (node (ref "C119") (pin "2") (pinfunction "2_2") (pintype "passive"))
      (node (ref "C120") (pin "2") (pinfunction "2_2") (pintype "passive"))
      (node (ref "C121") (pin "2") (pinfunction "2_2") (pintype "passive"))
      (node (ref "C122") (pin "2") (pinfunction "2_2") (pintype "passive"))
      (node (ref "C123") (pin "2") (pinfunction "2_2") (pintype "passive"))
      (node (ref "C124") (pin "2") (pinfunction "2_2") (pintype "passive"))
      (node (ref "C125") (pin "2") (pinfunction "2_2") (pintype "passive"))
      (node (ref "C126") (pin "2") (pinfunction "2_2") (pintype "passive"))
      (node (ref "C127") (pin "2") (pinfunction "2_2") (pintype "passive"))
      (node (ref "C128") (pin "2") (pinfunction "2_2") (pintype "passive"))
      (node (ref "C129") (pin "2") (pinfunction "2_2") (pintype "passive"))
      (node (ref "C130") (pin "2") (pinfunction "2_2") (pintype "passive"))
      (node (ref "C131") (pin "2") (pinfunction "2_2") (pintype "passive"))
      (node (ref "C132") (pin "2") (pinfunction "2_2") (pintype "passive"))
      (node (ref "C133") (pin "2") (pinfunction "2_2") (pintype "passive"))
      (node (ref "C134") (pin "2") (pinfunction "2_2") (pintype "passive"))
      (node (ref "C135") (pin "2") (pinfunction "2_2") (pintype "passive"))
      (node (ref "C136") (pin "2") (pinfunction "2_2") (pintype "passive"))
      (node (ref "C137") (pin "2") (pinfunction "2_2") (pintype "passive"))
      (node (ref "C138") (pin "2") (pinfunction "2_2") (pintype "passive"))
      (node (ref "C139") (pin "2") (pinfunction "2_2") (pintype "passive"))
      (node (ref "C140") (pin "2") (pinfunction "2_2") (pintype "passive"))
      (node (ref "C141") (pin "2") (pinfunction "2_2") (pintype "passive"))
      (node (ref "C142") (pin "2") (pinfunction "2_2") (pintype "passive"))
      (node (ref "C143") (pin "2") (pinfunction "2_2") (pintype "passive"))
      (node (ref "C144") (pin "2") (pinfunction "2_2") (pintype "passive"))
      (node (ref "C145") (pin "2") (pinfunction "2_2") (pintype "passive"))
      (node (ref "C146") (pin "2") (pinfunction "2_2") (pintype "passive"))
      (node (ref "C147") (pin "2") (pinfunction "2_2") (pintype "passive"))
      (node (ref "C148") (pin "2") (pinfunction "2_2") (pintype "passive"))
      (node (ref "C99") (pin "2") (pinfunction "2_2") (pintype "passive"))
      (node (ref "D1") (pin "1") (pinfunction "A_1") (pintype "passive"))
      (node (ref "D2") (pin "1") (pinfunction "A_1") (pintype "passive"))
      (node (ref "HEAT2") (pin "1") (pintype "passive"))
      (node (ref "HEAT2") (pin "2") (pintype "passive"))
      (node (ref "J2") (pin "1") (pinfunction "1_1") (pintype "passive"))
      (node (ref "R51") (pin "2") (pinfunction "2_2") (pintype "passive"))
      (node (ref "R52") (pin "1") (pinfunction "1_1") (pintype "passive"))
      (node (ref "R53") (pin "2") (pinfunction "2_2") (pintype "passive"))
      (node (ref "U2") (pin "4") (pinfunction "VSS_4") (pintype "power_in"))
      (node (ref "U3") (pin "2") (pinfunction "GND_2") (pintype "power_in"))
      (node (ref "U4") (pin "A1") (pinfunction "GND_A1") (pintype "power_in"))
      (node (ref "U4") (pin "A26") (pinfunction "GND_A26") (pintype "power_in"))
      (node (ref "U4") (pin "AB12") (pinfunction "GND_AB12") (pintype "power_in"))
      (node (ref "U4") (pin "AB16") (pinfunction "GND_AB16") (pintype "power_in"))
      (node (ref "U4") (pin "AB2") (pinfunction "GND_AB2") (pintype "power_in"))
      (node (ref "U4") (pin "AB20") (pinfunction "GND_AB20") (pintype "power_in"))
      (node (ref "U4") (pin "AB25") (pinfunction "GND_AB25") (pintype "power_in"))
      (node (ref "U4") (pin "AC8") (pinfunction "GND_AC8") (pintype "power_in"))
      (node (ref "U4") (pin "AE10") (pinfunction "GND_AE10") (pintype "power_in"))
      (node (ref "U4") (pin "AE14") (pinfunction "GND_AE14") (pintype "power_in"))
      (node (ref "U4") (pin "AE18") (pinfunction "GND_AE18") (pintype "power_in"))
      (node (ref "U4") (pin "AE22") (pinfunction "GND_AE22") (pintype "power_in"))
      (node (ref "U4") (pin "AE6") (pinfunction "GND_AE6") (pintype "power_in"))
      (node (ref "U4") (pin "AF1") (pinfunction "GND_AF1") (pintype "power_in"))
      (node (ref "U4") (pin "AF26") (pinfunction "GND_AF26") (pintype "power_in"))
      (node (ref "U4") (pin "B13") (pinfunction "GND_B13") (pintype "power_in"))
      (node (ref "U4") (pin "B17") (pinfunction "GND_B17") (pintype "power_in"))
      (node (ref "U4") (pin "B21") (pinfunction "GND_B21") (pintype "power_in"))
      (node (ref "U4") (pin "B5") (pinfunction "GND_B5") (pintype "power_in"))
      (node (ref "U4") (pin "B9") (pinfunction "GND_B9") (pintype "power_in"))
      (node (ref "U4") (pin "D4") (pinfunction "GND_D4") (pintype "power_in"))
      (node (ref "U4") (pin "E11") (pinfunction "GND_E11") (pintype "power_in"))
      (node (ref "U4") (pin "E15") (pinfunction "GND_E15") (pintype "power_in"))
      (node (ref "U4") (pin "E22") (pinfunction "GND_E22") (pintype "power_in"))
      (node (ref "U4") (pin "E7") (pinfunction "GND_E7") (pintype "power_in"))
      (node (ref "U4") (pin "F19") (pinfunction "GND_F19") (pintype "power_in"))
      (node (ref "U4") (pin "F2") (pinfunction "GND_F2") (pintype "power_in"))
      (node (ref "U4") (pin "F25") (pinfunction "GND_F25") (pintype "power_in"))
      (node (ref "U4") (pin "H11") (pinfunction "GND_H11") (pintype "power_in"))
      (node (ref "U4") (pin "H23") (pinfunction "GND_H23") (pintype "power_in"))
      (node (ref "U4") (pin "H4") (pinfunction "GND_H4") (pintype "power_in"))
      (node (ref "U4") (pin "J19") (pinfunction "GND_J19") (pintype "power_in"))
      (node (ref "U4") (pin "J8") (pinfunction "GND_J8") (pintype "power_in"))
      (node (ref "U4") (pin "K16") (pinfunction "GND_K16") (pintype "power_in"))
      (node (ref "U4") (pin "K2") (pinfunction "GND_K2") (pintype "power_in"))
      (node (ref "U4") (pin "K25") (pinfunction "GND_K25") (pintype "power_in"))
      (node (ref "U4") (pin "L11") (pinfunction "GND_L11") (pintype "power_in"))
      (node (ref "U4") (pin "L13") (pinfunction "GND_L13") (pintype "power_in"))
      (node (ref "U4") (pin "L15") (pinfunction "GND_L15") (pintype "power_in"))
      (node (ref "U4") (pin "M12") (pinfunction "GND_M12") (pintype "power_in"))
      (node (ref "U4") (pin "M14") (pinfunction "GND_M14") (pintype "power_in"))
      (node (ref "U4") (pin "M16") (pinfunction "GND_M16") (pintype "power_in"))
      (node (ref "U4") (pin "M22") (pinfunction "GND_M22") (pintype "power_in"))
      (node (ref "U4") (pin "M5") (pinfunction "GND_M5") (pintype "power_in"))
      (node (ref "U4") (pin "N11") (pinfunction "GND_N11") (pintype "power_in"))
      (node (ref "U4") (pin "N13") (pinfunction "GND_N13") (pintype "power_in"))
      (node (ref "U4") (pin "N15") (pinfunction "GND_N15") (pintype "power_in"))
      (node (ref "U4") (pin "P12") (pinfunction "GND_P12") (pintype "power_in"))
      (node (ref "U4") (pin "P14") (pinfunction "GND_P14") (pintype "power_in"))
      (node (ref "U4") (pin "P16") (pinfunction "GND_P16") (pintype "power_in"))
      (node (ref "U4") (pin "P19") (pinfunction "GND_P19") (pintype "power_in"))
      (node (ref "U4") (pin "P2") (pinfunction "GND_P2") (pintype "power_in"))
      (node (ref "U4") (pin "P25") (pinfunction "GND_P25") (pintype "power_in"))
      (node (ref "U4") (pin "R11") (pinfunction "GND_R11") (pintype "power_in"))
      (node (ref "U4") (pin "R13") (pinfunction "GND_R13") (pintype "power_in"))
      (node (ref "U4") (pin "R15") (pinfunction "GND_R15") (pintype "power_in"))
      (node (ref "U4") (pin "R8") (pinfunction "GND_R8") (pintype "power_in"))
      (node (ref "U4") (pin "T12") (pinfunction "GND_T12") (pintype "power_in"))
      (node (ref "U4") (pin "T14") (pinfunction "GND_T14") (pintype "power_in"))
      (node (ref "U4") (pin "T16") (pinfunction "GND_T16") (pintype "power_in"))
      (node (ref "U4") (pin "T21") (pinfunction "GND_T21") (pintype "power_in"))
      (node (ref "U4") (pin "T5") (pinfunction "GND_T5") (pintype "power_in"))
      (node (ref "U4") (pin "U11") (pinfunction "GND_U11") (pintype "power_in"))
      (node (ref "U4") (pin "V2") (pinfunction "GND_V2") (pintype "power_in"))
      (node (ref "U4") (pin "V25") (pinfunction "GND_V25") (pintype "power_in"))
      (node (ref "U4") (pin "W15") (pinfunction "GND_W15") (pintype "power_in"))
      (node (ref "U4") (pin "W20") (pinfunction "GND_W20") (pintype "power_in"))
      (node (ref "U4") (pin "Y11") (pinfunction "GND_Y11") (pintype "power_in"))
      (node (ref "U4") (pin "Y23") (pinfunction "GND_Y23") (pintype "power_in"))
      (node (ref "U4") (pin "Y4") (pinfunction "GND_Y4") (pintype "power_in"))
      (node (ref "U4") (pin "Y7") (pinfunction "GND_Y7") (pintype "power_in"))
    )
    (net (code "32") (name "Net-(J1-Pad1)") (class "Default")
      (node (ref "J1") (pin "1") (pinfunction "1_1") (pintype "passive"))
      (node (ref "R50") (pin "1") (pinfunction "1_1") (pintype "passive"))
    )
    (net (code "33") (name "Net-(J2-Pad3)") (class "Default")
      (node (ref "J2") (pin "3") (pinfunction "3_3") (pintype "passive"))
      (node (ref "R54") (pin "2") (pinfunction "2_2") (pintype "passive"))
    )
    (net (code "34") (name "Net-(J2-Pad4)") (class "Default")
      (node (ref "J2") (pin "4") (pinfunction "4_4") (pintype "passive"))
      (node (ref "R55") (pin "2") (pinfunction "2_2") (pintype "passive"))
    )
    (net (code "35") (name "Net-(R50-Pad2)") (class "Default")
      (node (ref "R50") (pin "2") (pinfunction "2_2") (pintype "passive"))
      (node (ref "R53") (pin "1") (pinfunction "1_1") (pintype "passive"))
    )
    (net (code "36") (name "Net-(TP11-A)") (class "Default")
      (node (ref "J4") (pin "1") (pinfunction "1_1") (pintype "passive"))
      (node (ref "TP11") (pin "1") (pinfunction "A_1") (pintype "passive"))
      (node (ref "U3") (pin "1") (pinfunction "WDO_1") (pintype "output"))
    )
    (net (code "37") (name "Net-(U2-X1)") (class "Default")
      (node (ref "C99") (pin "1") (pinfunction "1_1") (pintype "passive"))
      (node (ref "U2") (pin "1") (pinfunction "X1_1") (pintype "input"))
      (node (ref "X1") (pin "1") (pinfunction "1_1") (pintype "passive"))
    )
    (net (code "38") (name "Net-(U2-X2)") (class "Default")
      (node (ref "C103") (pin "1") (pinfunction "1_1") (pintype "passive"))
      (node (ref "U2") (pin "2") (pinfunction "X2_2") (pintype "output"))
      (node (ref "X1") (pin "2") (pinfunction "2_2") (pintype "passive"))
    )
    (net (code "39") (name "unconnected-(BT2-Pad+)") (class "Default")
      (node (ref "BT2") (pin "+") (pinfunction "+_+") (pintype "power_in+no_connect"))
    )
    (net (code "40") (name "unconnected-(BT2-Pad-)") (class "Default")
      (node (ref "BT2") (pin "-") (pinfunction "-_-") (pintype "power_in+no_connect"))
    )
    (net (code "41") (name "unconnected-(U4J-NC-PadE12)") (class "Default")
      (node (ref "U4") (pin "E12") (pinfunction "NC_E12") (pintype "passive+no_connect"))
    )
    (net (code "42") (name "unconnected-(U4J-NC-PadF8)") (class "Default")
      (node (ref "U4") (pin "F8") (pinfunction "NC_F8") (pintype "passive+no_connect"))
    )
    (net (code "43") (name "unconnected-(U4J-NC-PadF12)") (class "Default")
      (node (ref "U4") (pin "F12") (pinfunction "NC_F12") (pintype "passive+no_connect"))
    )
    (net (code "44") (name "unconnected-(U4J-NC-PadF14)") (class "Default")
      (node (ref "U4") (pin "F14") (pinfunction "NC_F14") (pintype "passive+no_connect"))
    )
    (net (code "45") (name "unconnected-(U4J-NC-PadG9)") (class "Default")
      (node (ref "U4") (pin "G9") (pinfunction "NC_G9") (pintype "passive+no_connect"))
    )
    (net (code "46") (name "unconnected-(U4J-NC-PadG11)") (class "Default")
      (node (ref "U4") (pin "G11") (pinfunction "NC_G11") (pintype "passive+no_connect"))
    )
    (net (code "47") (name "unconnected-(U4J-NC-PadG13)") (class "Default")
      (node (ref "U4") (pin "G13") (pinfunction "NC_G13") (pintype "passive+no_connect"))
    )
    (net (code "48") (name "unconnected-(U4J-NC-PadH9)") (class "Default")
      (node (ref "U4") (pin "H9") (pinfunction "NC_H9") (pintype "passive+no_connect"))
    )
    (net (code "49") (name "unconnected-(U4J-NC-PadH10)") (class "Default")
      (node (ref "U4") (pin "H10") (pinfunction "NC_H10") (pintype "passive+no_connect"))
    )
    (net (code "50") (name "unconnected-(U4J-NC-PadH12)") (class "Default")
      (node (ref "U4") (pin "H12") (pinfunction "NC_H12") (pintype "passive+no_connect"))
    )
    (net (code "51") (name "unconnected-(U4J-NC-PadH13)") (class "Default")
      (node (ref "U4") (pin "H13") (pinfunction "NC_H13") (pintype "passive+no_connect"))
    )
    (net (code "52") (name "unconnected-(U4J-NC-PadJ11)") (class "Default")
      (node (ref "U4") (pin "J11") (pinfunction "NC_J11") (pintype "passive+no_connect"))
    )
    (net (code "53") (name "unconnected-(U4J-NC-PadJ12)") (class "Default")
      (node (ref "U4") (pin "J12") (pinfunction "NC_J12") (pintype "passive+no_connect"))
    )
    (net (code "54") (name "unconnected-(U4J-NC-PadJ13)") (class "Default")
      (node (ref "U4") (pin "J13") (pinfunction "NC_J13") (pintype "passive+no_connect"))
    )
    (net (code "55") (name "unconnected-(U4J-NC-PadJ16)") (class "Default")
      (node (ref "U4") (pin "J16") (pinfunction "NC_J16") (pintype "passive+no_connect"))
    )
    (net (code "56") (name "unconnected-(U4J-NC-PadK12)") (class "Default")
      (node (ref "U4") (pin "K12") (pinfunction "NC_K12") (pintype "passive+no_connect"))
    )
    (net (code "57") (name "unconnected-(U4J-NC-PadK14)") (class "Default")
      (node (ref "U4") (pin "K14") (pinfunction "NC_K14") (pintype "passive+no_connect"))
    )
    (net (code "58") (name "unconnected-(U4J-NC-PadK15)") (class "Default")
      (node (ref "U4") (pin "K15") (pinfunction "NC_K15") (pintype "passive+no_connect"))
    )
  )
)
